# 180V_StepUp.net
KiCad netlist of a schematic drawn in EAGLE
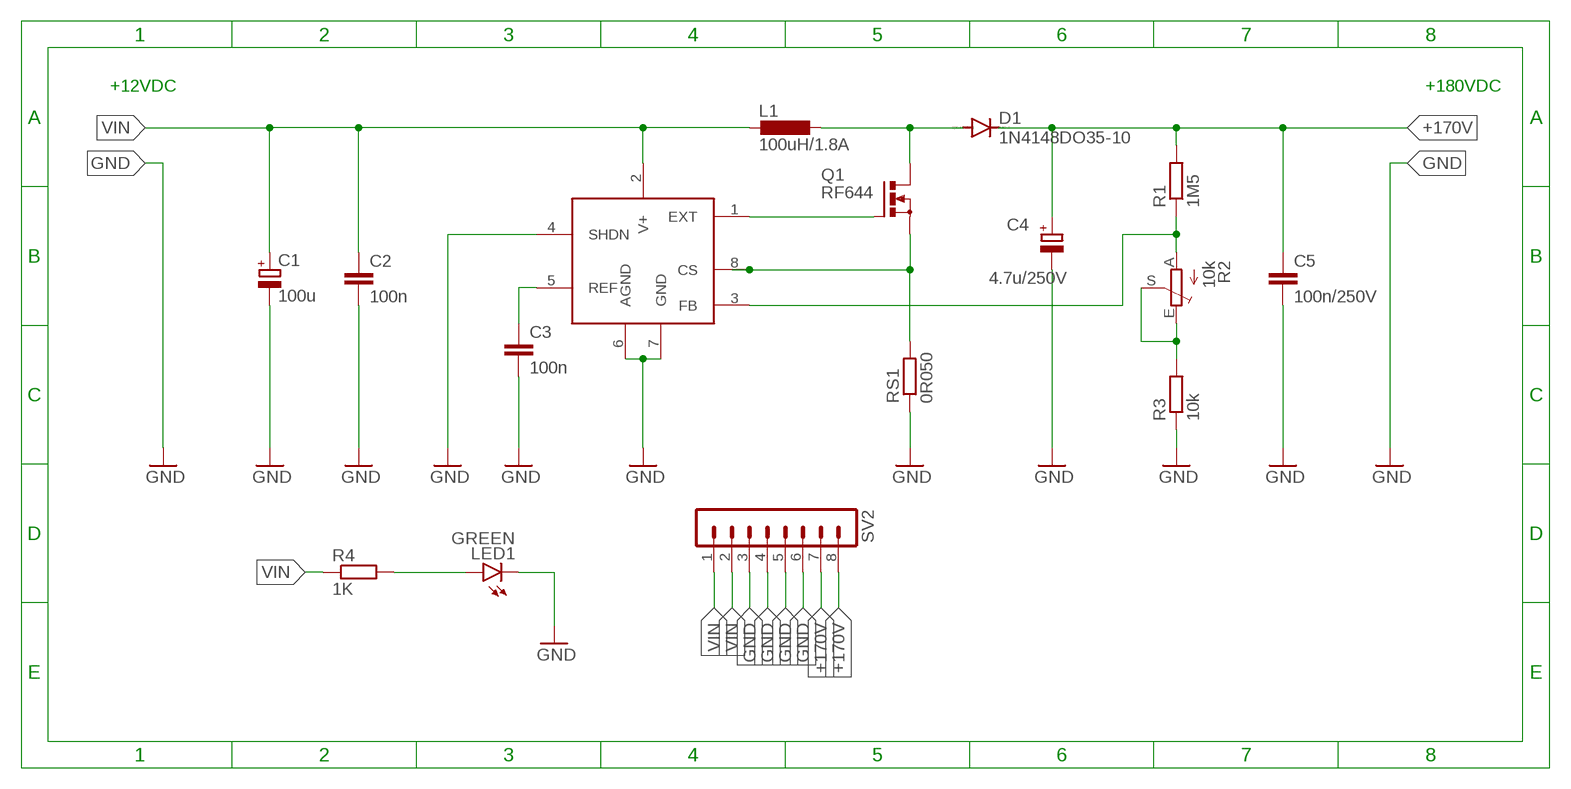
[diagram p0: schematic, sheet 1]
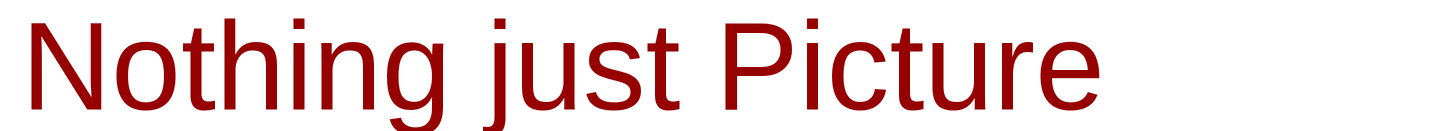
[diagram p1: schematic, sheet 2]

(export (version "E")
  (design (tool "Eeschema 10.0.6"))
  (components
    (comp (ref "C1")
      (value "100u")
      (footprint "eagle-import:E2,5-7")
      (libsource (lib "eagle-import") (part "CPOL-EUE2.5-7"))
    )
    (comp (ref "C2")
      (value "100n")
      (footprint "eagle-import:C0805")
      (libsource (lib "eagle-import") (part "C-EUC0805"))
    )
    (comp (ref "C3")
      (value "100n")
      (footprint "eagle-import:C0805")
      (libsource (lib "eagle-import") (part "C-EUC0805"))
    )
    (comp (ref "C4")
      (value "4.7u/250V")
      (footprint "eagle-import:E2,5-7")
      (libsource (lib "eagle-import") (part "CPOL-EUE2.5-7"))
    )
    (comp (ref "C5")
      (value "100n/250V")
      (footprint "eagle-import:C2225K")
      (libsource (lib "eagle-import") (part "C-EUC2225K"))
    )
    (comp (ref "D1")
      (value "1N4148DO35-10")
      (footprint "eagle-import:DO35-10")
      (libsource (lib "eagle-import") (part "1N4148DO35-10"))
    )
    (comp (ref "IC1")
      (value "MAX1771")
      (footprint "eagle-import:SO08")
      (libsource (lib "eagle-import") (part "MAX1771"))
    )
    (comp (ref "L1")
      (value "100uH/1.8A")
      (footprint "eagle-import:DO3316P")
      (libsource (lib "eagle-import") (part "DO3316P"))
    )
    (comp (ref "LED1")
      (value "GREEN")
      (footprint "eagle-import:1206")
      (libsource (lib "eagle-import") (part "LED_1206SMT1206"))
    )
    (comp (ref "Q1")
      (value "RF644")
      (footprint "eagle-import:TO220BV")
      (libsource (lib "eagle-import") (part "PMOSFET_NTO220BV"))
    )
    (comp (ref "R1")
      (value "1M5")
      (footprint "eagle-import:R0805")
      (libsource (lib "eagle-import") (part "R-EU_R0805"))
    )
    (comp (ref "R2")
      (value "10k")
      (footprint "eagle-import:RJ9W")
      (libsource (lib "eagle-import") (part "TRIM_EU-RJ9W"))
    )
    (comp (ref "R3")
      (value "10k")
      (footprint "eagle-import:R0805")
      (libsource (lib "eagle-import") (part "R-EU_R0805"))
    )
    (comp (ref "R4")
      (value "1K")
      (footprint "eagle-import:R1206")
      (libsource (lib "eagle-import") (part "R-EU_1206R1206"))
    )
    (comp (ref "RS1")
      (value "0R050")
      (footprint "eagle-import:0207_10")
      (libsource (lib "eagle-import") (part "R-EU_0207/10"))
    )
    (comp (ref "SV2")
      (value "MA08-1")
      (footprint "eagle-import:MA08-1")
      (libsource (lib "eagle-import") (part "MA08-1"))
    )
  )
  (nets
    (net (code "1") (name "+170V") (class "Default")
      (node (ref "C4") (pin "+") (pinfunction "+_+") (pintype "passive"))
      (node (ref "C5") (pin "1") (pinfunction "1_1") (pintype "passive"))
      (node (ref "D1") (pin "C") (pinfunction "C_C") (pintype "passive"))
      (node (ref "R1") (pin "2") (pinfunction "2_2") (pintype "passive"))
      (node (ref "SV2") (pin "7") (pinfunction "7_7") (pintype "passive"))
      (node (ref "SV2") (pin "8") (pinfunction "8_8") (pintype "passive"))
    )
    (net (code "2") (name "GND") (class "Default")
      (node (ref "C1") (pin "-") (pinfunction "-_-") (pintype "passive"))
      (node (ref "C2") (pin "2") (pinfunction "2_2") (pintype "passive"))
      (node (ref "C3") (pin "2") (pinfunction "2_2") (pintype "passive"))
      (node (ref "C4") (pin "-") (pinfunction "-_-") (pintype "passive"))
      (node (ref "C5") (pin "2") (pinfunction "2_2") (pintype "passive"))
      (node (ref "IC1") (pin "4") (pinfunction "SHDN_4") (pintype "bidirectional"))
      (node (ref "IC1") (pin "6") (pinfunction "AGND_6") (pintype "bidirectional"))
      (node (ref "IC1") (pin "7") (pinfunction "GND_7") (pintype "bidirectional"))
      (node (ref "LED1") (pin "C") (pinfunction "C_C") (pintype "passive"))
      (node (ref "R3") (pin "1") (pinfunction "1_1") (pintype "passive"))
      (node (ref "RS1") (pin "1") (pinfunction "1_1") (pintype "passive"))
      (node (ref "SV2") (pin "3") (pinfunction "3_3") (pintype "passive"))
      (node (ref "SV2") (pin "4") (pinfunction "4_4") (pintype "passive"))
      (node (ref "SV2") (pin "5") (pinfunction "5_5") (pintype "passive"))
      (node (ref "SV2") (pin "6") (pinfunction "6_6") (pintype "passive"))
    )
    (net (code "3") (name "Net-(D1-PadA)") (class "Default")
      (node (ref "D1") (pin "A") (pinfunction "A_A") (pintype "passive"))
      (node (ref "L1") (pin "2") (pinfunction "2_2") (pintype "passive"))
      (node (ref "Q1") (pin "D") (pinfunction "D_D") (pintype "passive"))
    )
    (net (code "4") (name "Net-(IC1-CS)") (class "Default")
      (node (ref "IC1") (pin "8") (pinfunction "CS_8") (pintype "bidirectional"))
      (node (ref "Q1") (pin "S") (pinfunction "S_S") (pintype "passive"))
      (node (ref "RS1") (pin "2") (pinfunction "2_2") (pintype "passive"))
    )
    (net (code "5") (name "Net-(IC1-EXT)") (class "Default")
      (node (ref "IC1") (pin "1") (pinfunction "EXT_1") (pintype "bidirectional"))
      (node (ref "Q1") (pin "G") (pinfunction "G_G") (pintype "passive"))
    )
    (net (code "6") (name "Net-(IC1-FB)") (class "Default")
      (node (ref "IC1") (pin "3") (pinfunction "FB_3") (pintype "bidirectional"))
      (node (ref "R1") (pin "1") (pinfunction "1_1") (pintype "passive"))
      (node (ref "R2") (pin "A") (pinfunction "A_A") (pintype "passive"))
    )
    (net (code "7") (name "Net-(IC1-REF)") (class "Default")
      (node (ref "C3") (pin "1") (pinfunction "1_1") (pintype "passive"))
      (node (ref "IC1") (pin "5") (pinfunction "REF_5") (pintype "bidirectional"))
    )
    (net (code "8") (name "Net-(LED1-PadA)") (class "Default")
      (node (ref "LED1") (pin "A") (pinfunction "A_A") (pintype "passive"))
      (node (ref "R4") (pin "2") (pinfunction "2_2") (pintype "passive"))
    )
    (net (code "9") (name "Net-(R2-PadE)") (class "Default")
      (node (ref "R2") (pin "E") (pinfunction "E_E") (pintype "passive"))
      (node (ref "R2") (pin "S") (pinfunction "S_S") (pintype "passive"))
      (node (ref "R3") (pin "2") (pinfunction "2_2") (pintype "passive"))
    )
    (net (code "10") (name "VIN") (class "Default")
      (node (ref "C1") (pin "+") (pinfunction "+_+") (pintype "passive"))
      (node (ref "C2") (pin "1") (pinfunction "1_1") (pintype "passive"))
      (node (ref "IC1") (pin "2") (pinfunction "V+_2") (pintype "bidirectional"))
      (node (ref "L1") (pin "1") (pinfunction "1_1") (pintype "passive"))
      (node (ref "R4") (pin "1") (pinfunction "1_1") (pintype "passive"))
      (node (ref "SV2") (pin "1") (pinfunction "1_1") (pintype "passive"))
      (node (ref "SV2") (pin "2") (pinfunction "2_2") (pintype "passive"))
    )
  )
)
